# main_low_pass.net
KiCad netlist of a schematic drawn in EAGLE
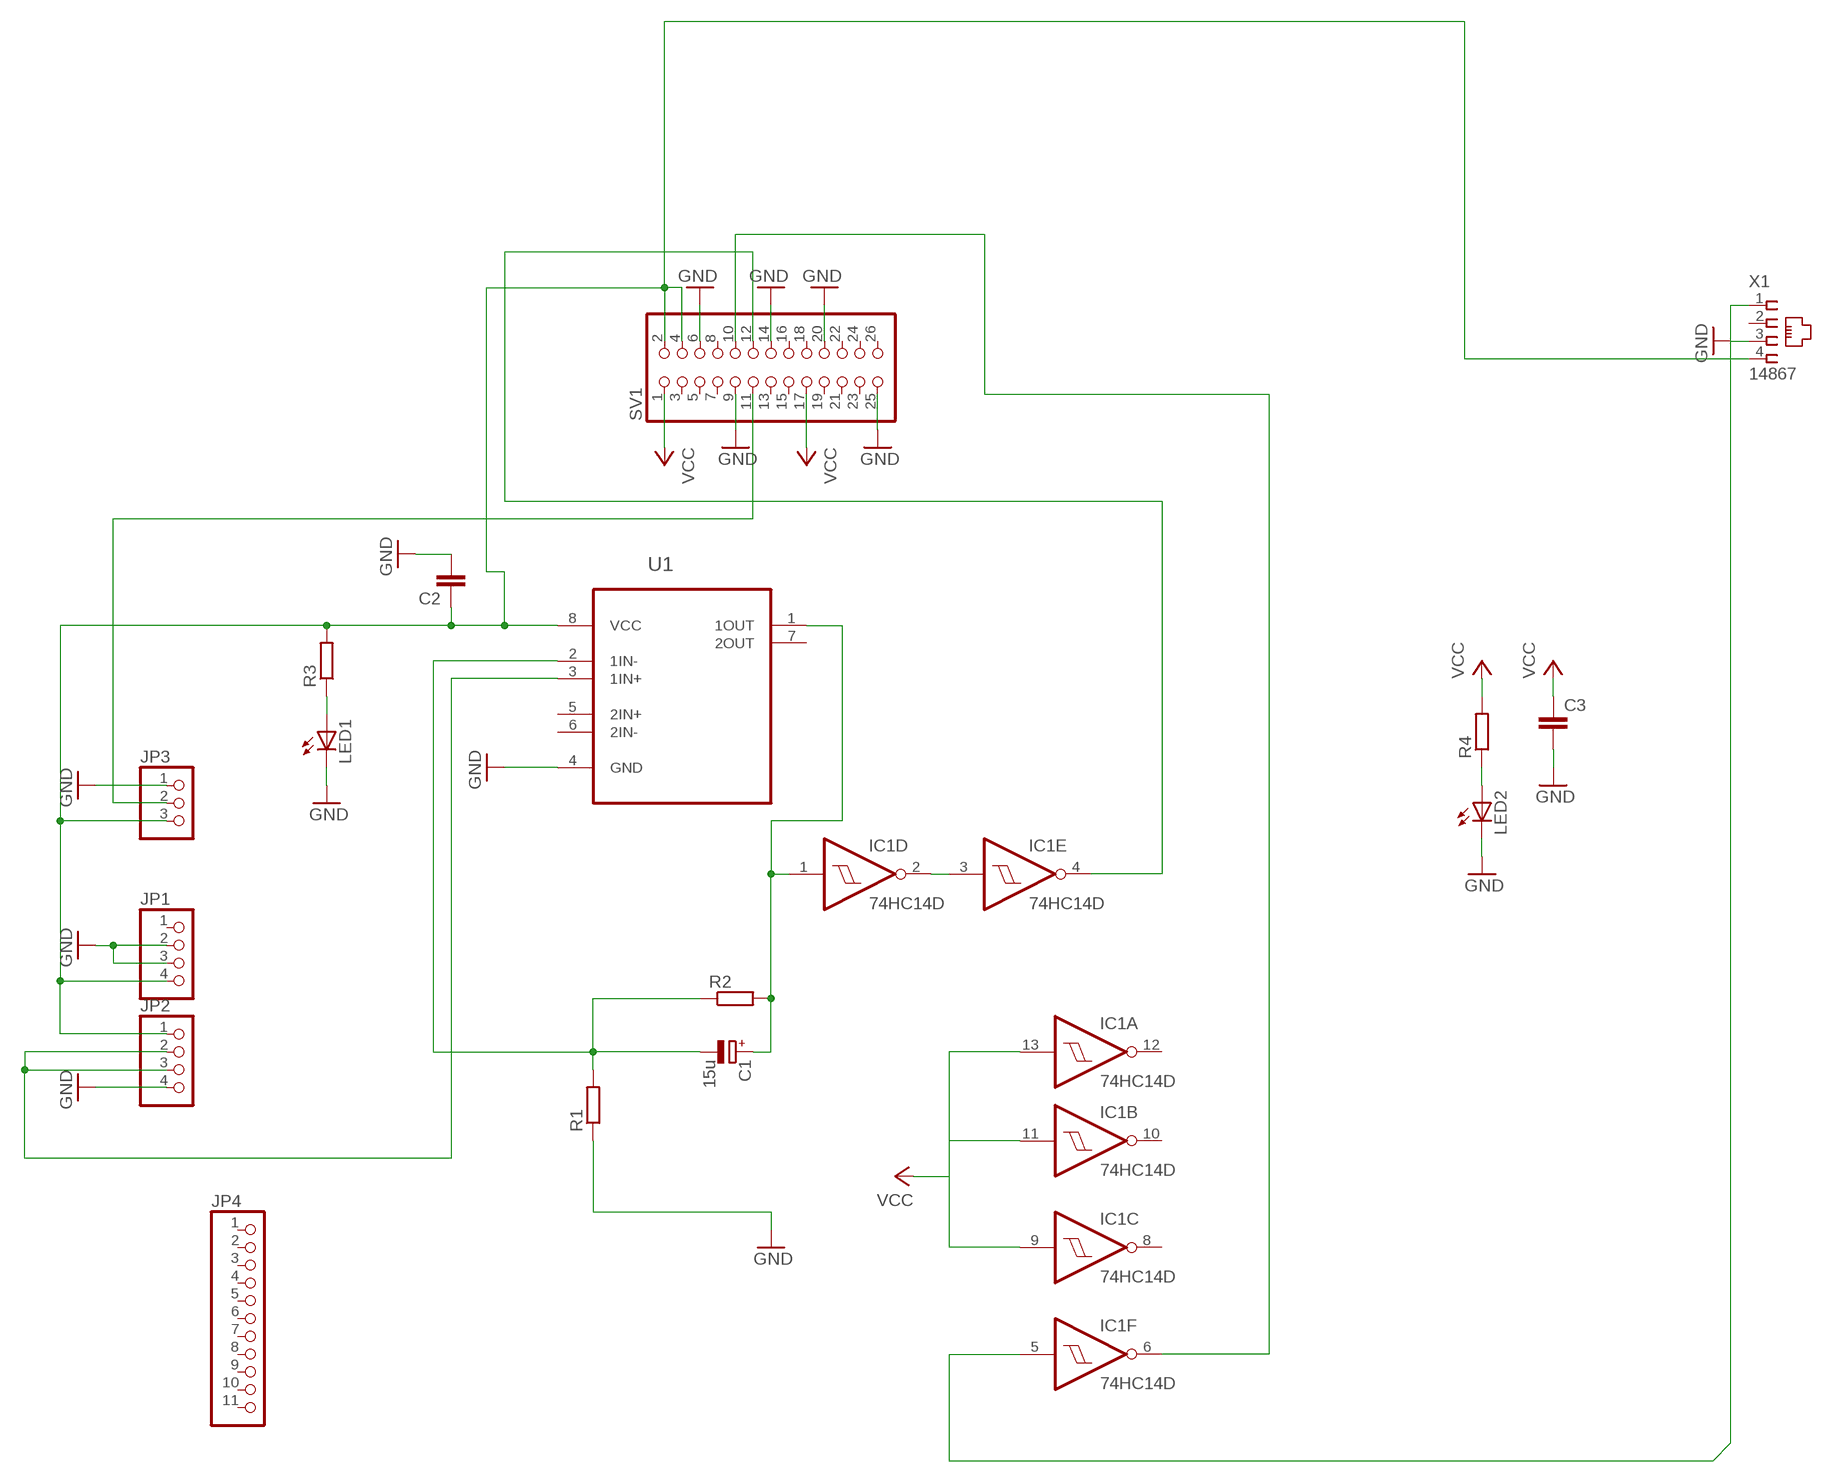
[diagram p0: schematic, sheet 1]

(export (version "E")
  (design (tool "Eeschema 10.0.6"))
  (components
    (comp (ref "C1")
      (value "15u")
      (footprint "eagle-import:153CLV-0605")
      (libsource (lib "eagle-import") (part "CPOL-EU153CLV-0605"))
    )
    (comp (ref "C2")
      (value "C-EUC0805")
      (footprint "eagle-import:C0805")
      (libsource (lib "eagle-import") (part "C-EUC0805"))
    )
    (comp (ref "C3")
      (value "C-EUC0805")
      (footprint "eagle-import:C0805")
      (libsource (lib "eagle-import") (part "C-EUC0805"))
    )
    (comp (ref "IC1")
      (value "74HC14D")
      (footprint "eagle-import:SO14")
      (libsource (lib "eagle-import") (part "7414DHC"))
    )
    (comp (ref "JP1")
      (value "PINHD-1X4")
      (footprint "eagle-import:1X04")
      (libsource (lib "eagle-import") (part "PINHD-1X4"))
    )
    (comp (ref "JP2")
      (value "PINHD-1X4")
      (footprint "eagle-import:1X04")
      (libsource (lib "eagle-import") (part "PINHD-1X4"))
    )
    (comp (ref "JP3")
      (value "PINHD-1X3")
      (footprint "eagle-import:1X03")
      (libsource (lib "eagle-import") (part "PINHD-1X3"))
    )
    (comp (ref "JP4")
      (value "PINHD-1X11")
      (footprint "eagle-import:1X11")
      (libsource (lib "eagle-import") (part "PINHD-1X11"))
    )
    (comp (ref "LED1")
      (value "LEDCHIP-LED0805")
      (footprint "eagle-import:CHIP-LED0805")
      (libsource (lib "eagle-import") (part "LEDCHIP-LED0805"))
    )
    (comp (ref "LED2")
      (value "LEDCHIP-LED0805")
      (footprint "eagle-import:CHIP-LED0805")
      (libsource (lib "eagle-import") (part "LEDCHIP-LED0805"))
    )
    (comp (ref "R1")
      (value "R-EU_R0805")
      (footprint "eagle-import:R0805")
      (libsource (lib "eagle-import") (part "R-EU_R0805"))
    )
    (comp (ref "R2")
      (value "R-EU_R0805")
      (footprint "eagle-import:R0805")
      (libsource (lib "eagle-import") (part "R-EU_R0805"))
    )
    (comp (ref "R3")
      (value "R-EU_R0805")
      (footprint "eagle-import:R0805")
      (libsource (lib "eagle-import") (part "R-EU_R0805"))
    )
    (comp (ref "R4")
      (value "R-EU_R0805")
      (footprint "eagle-import:R0805")
      (libsource (lib "eagle-import") (part "R-EU_R0805"))
    )
    (comp (ref "SV1")
      (value "PINHD-2X13")
      (footprint "eagle-import:2X13")
      (libsource (lib "eagle-import") (part "PINHD-2X13"))
    )
    (comp (ref "U1")
      (value "LM358PW")
      (footprint "eagle-import:SOP65P640X120-8N")
      (libsource (lib "eagle-import") (part "LM358PW"))
    )
    (comp (ref "X1")
      (value "14867")
      (footprint "eagle-import:14867")
      (libsource (lib "eagle-import") (part "14867"))
    )
  )
  (nets
    (net (code "1") (name "GND") (class "Default")
      (node (ref "C2") (pin "2") (pinfunction "2_2") (pintype "passive"))
      (node (ref "C3") (pin "2") (pinfunction "2_2") (pintype "passive"))
      (node (ref "JP1") (pin "2") (pinfunction "2_2") (pintype "passive"))
      (node (ref "JP1") (pin "3") (pinfunction "3_3") (pintype "passive"))
      (node (ref "JP2") (pin "4") (pinfunction "4_4") (pintype "passive"))
      (node (ref "JP3") (pin "1") (pinfunction "1_1") (pintype "passive"))
      (node (ref "LED1") (pin "C") (pinfunction "C_C") (pintype "passive"))
      (node (ref "LED2") (pin "C") (pinfunction "C_C") (pintype "passive"))
      (node (ref "R1") (pin "1") (pinfunction "1_1") (pintype "passive"))
      (node (ref "SV1") (pin "14") (pinfunction "14_14") (pintype "passive"))
      (node (ref "SV1") (pin "20") (pinfunction "20_20") (pintype "passive"))
      (node (ref "SV1") (pin "25") (pinfunction "25_25") (pintype "passive"))
      (node (ref "SV1") (pin "6") (pinfunction "6_6") (pintype "passive"))
      (node (ref "SV1") (pin "9") (pinfunction "9_9") (pintype "passive"))
      (node (ref "U1") (pin "4") (pinfunction "GND_4") (pintype "passive"))
      (node (ref "X1") (pin "3") (pinfunction "3_3") (pintype "passive"))
    )
    (net (code "2") (name "Net-(IC1D-I)") (class "Default")
      (node (ref "C1") (pin "+") (pinfunction "+_+") (pintype "passive"))
      (node (ref "IC1") (pin "1") (pinfunction "I_1") (pintype "input"))
      (node (ref "R2") (pin "2") (pinfunction "2_2") (pintype "passive"))
      (node (ref "U1") (pin "1") (pinfunction "1OUT_1") (pintype "output"))
    )
    (net (code "3") (name "Net-(IC1D-O)") (class "Default")
      (node (ref "IC1") (pin "2") (pinfunction "O_2") (pintype "output"))
      (node (ref "IC1") (pin "3") (pinfunction "I_3") (pintype "input"))
    )
    (net (code "4") (name "Net-(IC1E-O)") (class "Default")
      (node (ref "IC1") (pin "4") (pinfunction "O_4") (pintype "output"))
      (node (ref "SV1") (pin "12") (pinfunction "12_12") (pintype "passive"))
    )
    (net (code "5") (name "Net-(IC1F-I)") (class "Default")
      (node (ref "IC1") (pin "5") (pinfunction "I_5") (pintype "input"))
      (node (ref "X1") (pin "1") (pinfunction "1_1") (pintype "passive"))
    )
    (net (code "6") (name "Net-(IC1F-O)") (class "Default")
      (node (ref "IC1") (pin "6") (pinfunction "O_6") (pintype "output"))
      (node (ref "SV1") (pin "10") (pinfunction "10_10") (pintype "passive"))
    )
    (net (code "7") (name "Net-(JP3-Pad2)") (class "Default")
      (node (ref "JP3") (pin "2") (pinfunction "2_2") (pintype "passive"))
      (node (ref "SV1") (pin "11") (pinfunction "11_11") (pintype "passive"))
    )
    (net (code "8") (name "Net-(LED1-PadA)") (class "Default")
      (node (ref "LED1") (pin "A") (pinfunction "A_A") (pintype "passive"))
      (node (ref "R3") (pin "1") (pinfunction "1_1") (pintype "passive"))
    )
    (net (code "9") (name "Net-(LED2-PadA)") (class "Default")
      (node (ref "LED2") (pin "A") (pinfunction "A_A") (pintype "passive"))
      (node (ref "R4") (pin "1") (pinfunction "1_1") (pintype "passive"))
    )
    (net (code "10") (name "Net-(U1-1IN+)") (class "Default")
      (node (ref "JP2") (pin "2") (pinfunction "2_2") (pintype "passive"))
      (node (ref "JP2") (pin "3") (pinfunction "3_3") (pintype "passive"))
      (node (ref "U1") (pin "3") (pinfunction "1IN+_3") (pintype "input"))
    )
    (net (code "11") (name "Net-(U1-1IN-)") (class "Default")
      (node (ref "C1") (pin "-") (pinfunction "-_-") (pintype "passive"))
      (node (ref "R1") (pin "2") (pinfunction "2_2") (pintype "passive"))
      (node (ref "R2") (pin "1") (pinfunction "1_1") (pintype "passive"))
      (node (ref "U1") (pin "2") (pinfunction "1IN-_2") (pintype "input"))
    )
    (net (code "12") (name "Net-(U1-VCC)") (class "Default")
      (node (ref "C2") (pin "1") (pinfunction "1_1") (pintype "passive"))
      (node (ref "JP1") (pin "4") (pinfunction "4_4") (pintype "passive"))
      (node (ref "JP2") (pin "1") (pinfunction "1_1") (pintype "passive"))
      (node (ref "JP3") (pin "3") (pinfunction "3_3") (pintype "passive"))
      (node (ref "R3") (pin "2") (pinfunction "2_2") (pintype "passive"))
      (node (ref "SV1") (pin "2") (pinfunction "2_2") (pintype "passive"))
      (node (ref "SV1") (pin "4") (pinfunction "4_4") (pintype "passive"))
      (node (ref "U1") (pin "8") (pinfunction "VCC_8") (pintype "power_in"))
      (node (ref "X1") (pin "4") (pinfunction "4_4") (pintype "passive"))
    )
    (net (code "13") (name "VCC") (class "Default")
      (node (ref "C3") (pin "1") (pinfunction "1_1") (pintype "passive"))
      (node (ref "IC1") (pin "11") (pinfunction "I_11") (pintype "input"))
      (node (ref "IC1") (pin "13") (pinfunction "I_13") (pintype "input"))
      (node (ref "IC1") (pin "9") (pinfunction "I_9") (pintype "input"))
      (node (ref "R4") (pin "2") (pinfunction "2_2") (pintype "passive"))
      (node (ref "SV1") (pin "1") (pinfunction "1_1") (pintype "passive"))
      (node (ref "SV1") (pin "17") (pinfunction "17_17") (pintype "passive"))
    )
    (net (code "14") (name "unconnected-(IC1A-O-Pad12)") (class "Default")
      (node (ref "IC1") (pin "12") (pinfunction "O_12") (pintype "output"))
    )
    (net (code "15") (name "unconnected-(IC1B-O-Pad10)") (class "Default")
      (node (ref "IC1") (pin "10") (pinfunction "O_10") (pintype "output"))
    )
    (net (code "16") (name "unconnected-(IC1C-O-Pad8)") (class "Default")
      (node (ref "IC1") (pin "8") (pinfunction "O_8") (pintype "output"))
    )
    (net (code "17") (name "unconnected-(JP1-Pad1)") (class "Default")
      (node (ref "JP1") (pin "1") (pinfunction "1_1") (pintype "passive"))
    )
    (net (code "18") (name "unconnected-(JP4-Pad1)") (class "Default")
      (node (ref "JP4") (pin "1") (pinfunction "1_1") (pintype "passive"))
    )
    (net (code "19") (name "unconnected-(JP4-Pad2)") (class "Default")
      (node (ref "JP4") (pin "2") (pinfunction "2_2") (pintype "passive"))
    )
    (net (code "20") (name "unconnected-(JP4-Pad3)") (class "Default")
      (node (ref "JP4") (pin "3") (pinfunction "3_3") (pintype "passive"))
    )
    (net (code "21") (name "unconnected-(JP4-Pad4)") (class "Default")
      (node (ref "JP4") (pin "4") (pinfunction "4_4") (pintype "passive"))
    )
    (net (code "22") (name "unconnected-(JP4-Pad5)") (class "Default")
      (node (ref "JP4") (pin "5") (pinfunction "5_5") (pintype "passive"))
    )
    (net (code "23") (name "unconnected-(JP4-Pad6)") (class "Default")
      (node (ref "JP4") (pin "6") (pinfunction "6_6") (pintype "passive"))
    )
    (net (code "24") (name "unconnected-(JP4-Pad7)") (class "Default")
      (node (ref "JP4") (pin "7") (pinfunction "7_7") (pintype "passive"))
    )
    (net (code "25") (name "unconnected-(JP4-Pad8)") (class "Default")
      (node (ref "JP4") (pin "8") (pinfunction "8_8") (pintype "passive"))
    )
    (net (code "26") (name "unconnected-(JP4-Pad9)") (class "Default")
      (node (ref "JP4") (pin "9") (pinfunction "9_9") (pintype "passive"))
    )
    (net (code "27") (name "unconnected-(JP4-Pad10)") (class "Default")
      (node (ref "JP4") (pin "10") (pinfunction "10_10") (pintype "passive"))
    )
    (net (code "28") (name "unconnected-(JP4-Pad11)") (class "Default")
      (node (ref "JP4") (pin "11") (pinfunction "11_11") (pintype "passive"))
    )
    (net (code "29") (name "unconnected-(SV1-Pad3)") (class "Default")
      (node (ref "SV1") (pin "3") (pinfunction "3_3") (pintype "passive"))
    )
    (net (code "30") (name "unconnected-(SV1-Pad5)") (class "Default")
      (node (ref "SV1") (pin "5") (pinfunction "5_5") (pintype "passive"))
    )
    (net (code "31") (name "unconnected-(SV1-Pad7)") (class "Default")
      (node (ref "SV1") (pin "7") (pinfunction "7_7") (pintype "passive"))
    )
    (net (code "32") (name "unconnected-(SV1-Pad8)") (class "Default")
      (node (ref "SV1") (pin "8") (pinfunction "8_8") (pintype "passive"))
    )
    (net (code "33") (name "unconnected-(SV1-Pad13)") (class "Default")
      (node (ref "SV1") (pin "13") (pinfunction "13_13") (pintype "passive"))
    )
    (net (code "34") (name "unconnected-(SV1-Pad15)") (class "Default")
      (node (ref "SV1") (pin "15") (pinfunction "15_15") (pintype "passive"))
    )
    (net (code "35") (name "unconnected-(SV1-Pad16)") (class "Default")
      (node (ref "SV1") (pin "16") (pinfunction "16_16") (pintype "passive"))
    )
    (net (code "36") (name "unconnected-(SV1-Pad18)") (class "Default")
      (node (ref "SV1") (pin "18") (pinfunction "18_18") (pintype "passive"))
    )
    (net (code "37") (name "unconnected-(SV1-Pad19)") (class "Default")
      (node (ref "SV1") (pin "19") (pinfunction "19_19") (pintype "passive"))
    )
    (net (code "38") (name "unconnected-(SV1-Pad21)") (class "Default")
      (node (ref "SV1") (pin "21") (pinfunction "21_21") (pintype "passive"))
    )
    (net (code "39") (name "unconnected-(SV1-Pad22)") (class "Default")
      (node (ref "SV1") (pin "22") (pinfunction "22_22") (pintype "passive"))
    )
    (net (code "40") (name "unconnected-(SV1-Pad23)") (class "Default")
      (node (ref "SV1") (pin "23") (pinfunction "23_23") (pintype "passive"))
    )
    (net (code "41") (name "unconnected-(SV1-Pad24)") (class "Default")
      (node (ref "SV1") (pin "24") (pinfunction "24_24") (pintype "passive"))
    )
    (net (code "42") (name "unconnected-(SV1-Pad26)") (class "Default")
      (node (ref "SV1") (pin "26") (pinfunction "26_26") (pintype "passive"))
    )
    (net (code "43") (name "unconnected-(U1-2IN+-Pad5)") (class "Default")
      (node (ref "U1") (pin "5") (pinfunction "2IN+_5") (pintype "input"))
    )
    (net (code "44") (name "unconnected-(U1-2IN--Pad6)") (class "Default")
      (node (ref "U1") (pin "6") (pinfunction "2IN-_6") (pintype "input"))
    )
    (net (code "45") (name "unconnected-(U1-2OUT-Pad7)") (class "Default")
      (node (ref "U1") (pin "7") (pinfunction "2OUT_7") (pintype "output"))
    )
    (net (code "46") (name "unconnected-(X1-Pad2)") (class "Default")
      (node (ref "X1") (pin "2") (pinfunction "2_2") (pintype "passive"))
    )
  )
)
